# OSD_PCB.net
KiCad netlist of a schematic drawn in EAGLE
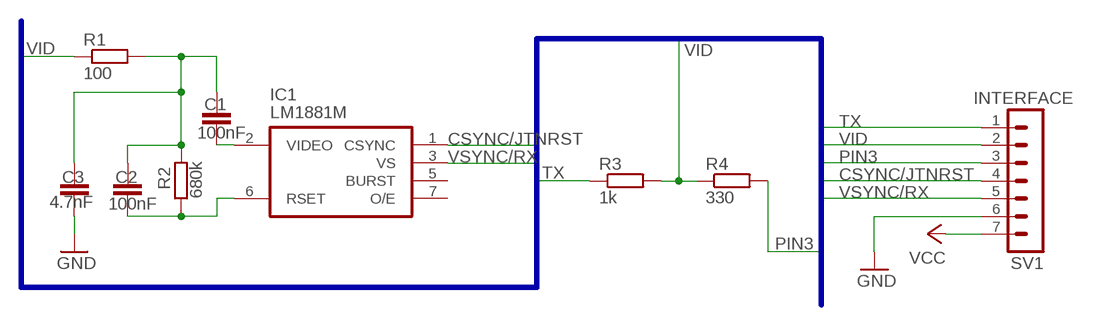
[diagram p0: schematic, sheet 1]

(export (version "E")
  (design (tool "Eeschema 10.0.6"))
  (components
    (comp (ref "C1")
      (value "100nF")
      (footprint "eagle-import:C0603")
      (libsource (lib "eagle-import") (part "C-EUC0603"))
    )
    (comp (ref "C2")
      (value "100nF")
      (footprint "eagle-import:C0603")
      (libsource (lib "eagle-import") (part "C-EUC0603"))
    )
    (comp (ref "C3")
      (value "4.7nF")
      (footprint "eagle-import:C0603")
      (libsource (lib "eagle-import") (part "C-EUC0603"))
    )
    (comp (ref "IC1")
      (value "LM1881M")
      (footprint "eagle-import:SO08")
      (libsource (lib "eagle-import") (part "LM1881M"))
    )
    (comp (ref "R1")
      (value "100")
      (footprint "eagle-import:R0603")
      (libsource (lib "eagle-import") (part "R-EU_R0603"))
    )
    (comp (ref "R2")
      (value "680k")
      (footprint "eagle-import:R0603")
      (libsource (lib "eagle-import") (part "R-EU_R0603"))
    )
    (comp (ref "R3")
      (value "1k")
      (footprint "eagle-import:R0603")
      (libsource (lib "eagle-import") (part "R-EU_R0603"))
    )
    (comp (ref "R4")
      (value "330")
      (footprint "eagle-import:R0603")
      (libsource (lib "eagle-import") (part "R-EU_R0603"))
    )
    (comp (ref "SV1")
      (value "INTERFACE")
      (footprint "eagle-import:MA07-1")
      (fields (field (name "SPICEPREFIX") "X"))
      (libsource (lib "eagle-import") (part "MA07-1"))
    )
  )
  (nets
    (net (code "1") (name "/CSYNC{slash}JTNRST") (class "Default")
      (node (ref "IC1") (pin "1") (pinfunction "CSYNC_1") (pintype "output"))
      (node (ref "SV1") (pin "4") (pinfunction "4_4") (pintype "passive"))
    )
    (net (code "2") (name "/PIN3") (class "Default")
      (node (ref "R4") (pin "2") (pinfunction "2_2") (pintype "passive"))
      (node (ref "SV1") (pin "3") (pinfunction "3_3") (pintype "passive"))
    )
    (net (code "3") (name "/TX") (class "Default")
      (node (ref "R3") (pin "1") (pinfunction "1_1") (pintype "passive"))
      (node (ref "SV1") (pin "1") (pinfunction "1_1") (pintype "passive"))
    )
    (net (code "4") (name "/VID") (class "Default")
      (node (ref "R1") (pin "1") (pinfunction "1_1") (pintype "passive"))
      (node (ref "R3") (pin "2") (pinfunction "2_2") (pintype "passive"))
      (node (ref "R4") (pin "1") (pinfunction "1_1") (pintype "passive"))
      (node (ref "SV1") (pin "2") (pinfunction "2_2") (pintype "passive"))
    )
    (net (code "5") (name "/VSYNC{slash}RX") (class "Default")
      (node (ref "IC1") (pin "3") (pinfunction "VS_3") (pintype "output"))
      (node (ref "SV1") (pin "5") (pinfunction "5_5") (pintype "passive"))
    )
    (net (code "6") (name "GND") (class "Default")
      (node (ref "C3") (pin "2") (pinfunction "2_2") (pintype "passive"))
      (node (ref "SV1") (pin "6") (pinfunction "6_6") (pintype "passive"))
    )
    (net (code "7") (name "Net-(C1-Pad1)") (class "Default")
      (node (ref "C1") (pin "1") (pinfunction "1_1") (pintype "passive"))
      (node (ref "C2") (pin "1") (pinfunction "1_1") (pintype "passive"))
      (node (ref "C3") (pin "1") (pinfunction "1_1") (pintype "passive"))
      (node (ref "R1") (pin "2") (pinfunction "2_2") (pintype "passive"))
      (node (ref "R2") (pin "2") (pinfunction "2_2") (pintype "passive"))
    )
    (net (code "8") (name "Net-(IC1A-RSET)") (class "Default")
      (node (ref "C2") (pin "2") (pinfunction "2_2") (pintype "passive"))
      (node (ref "IC1") (pin "6") (pinfunction "RSET_6") (pintype "passive"))
      (node (ref "R2") (pin "1") (pinfunction "1_1") (pintype "passive"))
    )
    (net (code "9") (name "Net-(IC1A-VIDEO)") (class "Default")
      (node (ref "C1") (pin "2") (pinfunction "2_2") (pintype "passive"))
      (node (ref "IC1") (pin "2") (pinfunction "VIDEO_2") (pintype "input"))
    )
    (net (code "10") (name "VCC") (class "Default")
      (node (ref "SV1") (pin "7") (pinfunction "7_7") (pintype "passive"))
    )
    (net (code "11") (name "unconnected-(IC1A-BURST-Pad5)") (class "Default")
      (node (ref "IC1") (pin "5") (pinfunction "BURST_5") (pintype "output"))
    )
    (net (code "12") (name "unconnected-(IC1A-O{slash}E-Pad7)") (class "Default")
      (node (ref "IC1") (pin "7") (pinfunction "O/E_7") (pintype "output"))
    )
  )
)
